# SensorTensao.net
KiCad netlist of a schematic drawn in EAGLE
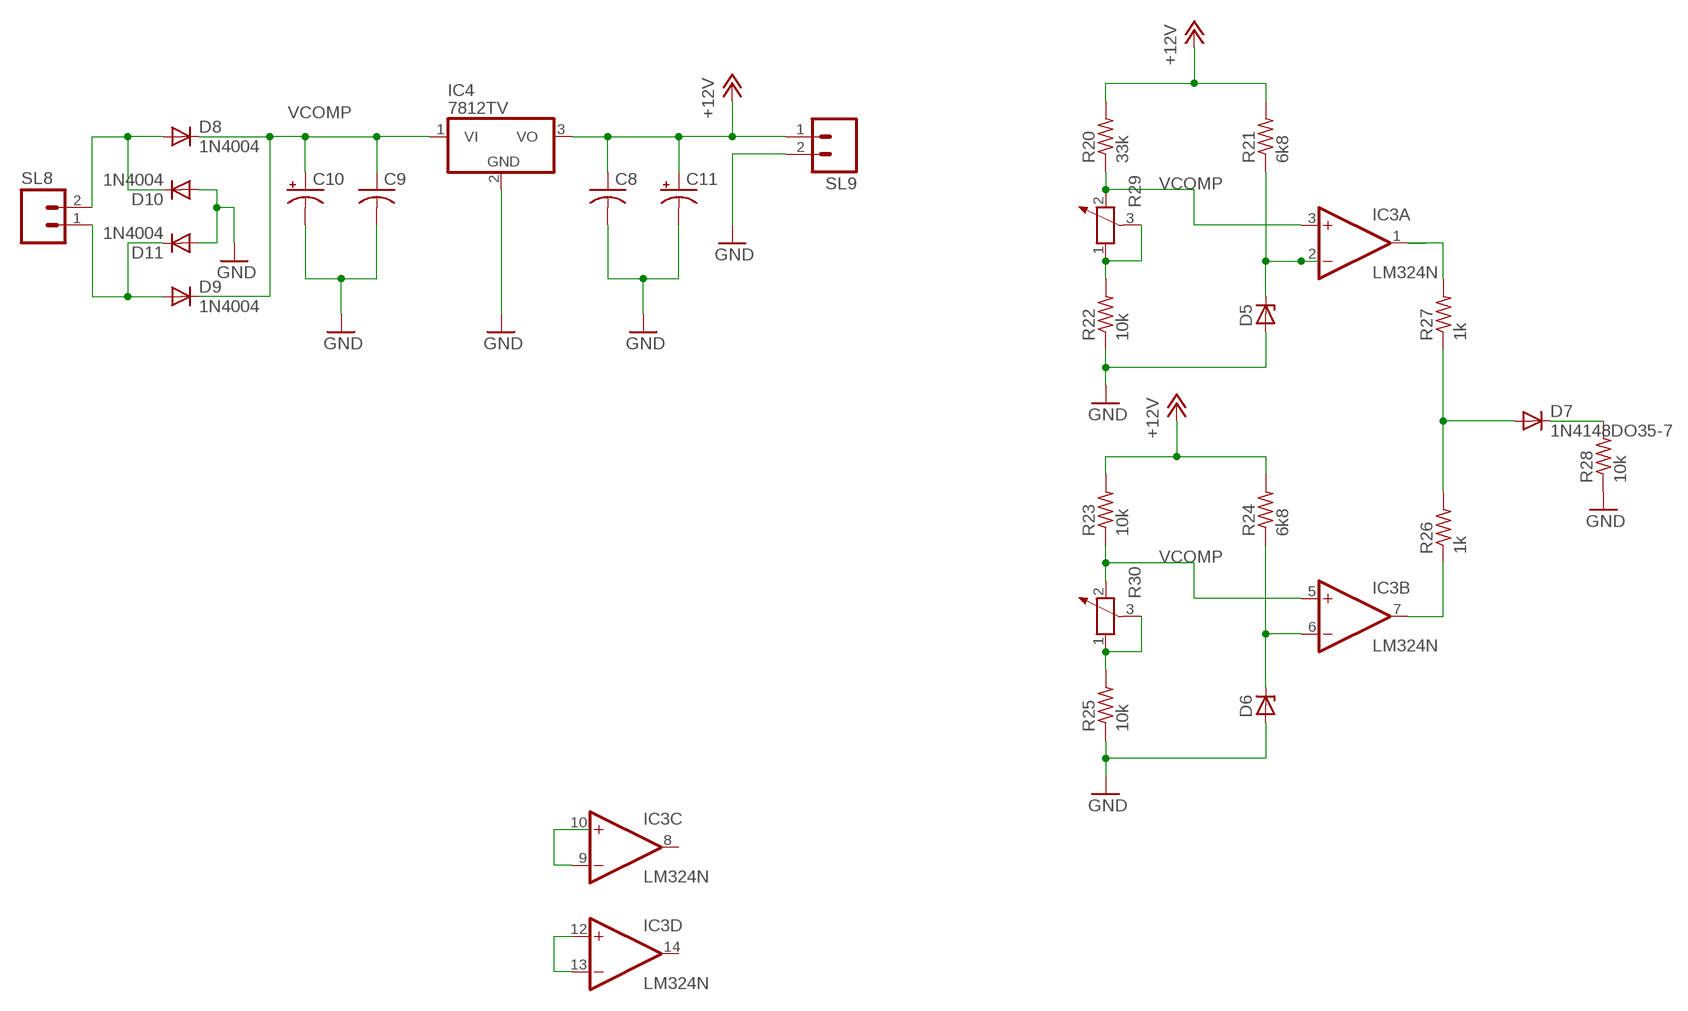
[diagram p0: schematic, sheet 1]

(export (version "E")
  (design (tool "Eeschema 10.0.6"))
  (components
    (comp (ref "C8")
      (value "C-US050-030X075")
      (footprint "eagle-import:C050-030X075")
      (libsource (lib "eagle-import") (part "C-US050-030X075"))
    )
    (comp (ref "C9")
      (value "C-US050-030X075")
      (footprint "eagle-import:C050-030X075")
      (libsource (lib "eagle-import") (part "C-US050-030X075"))
    )
    (comp (ref "C10")
      (value "CPOL-USE2.5-6")
      (footprint "eagle-import:E2,5-6")
      (libsource (lib "eagle-import") (part "CPOL-USE2.5-6"))
    )
    (comp (ref "C11")
      (value "CPOL-USE2.5-6")
      (footprint "eagle-import:E2,5-6")
      (libsource (lib "eagle-import") (part "CPOL-USE2.5-6"))
    )
    (comp (ref "D5")
      (value "ZENER-DIODEZD-7.5")
      (footprint "eagle-import:ZDIO-7.5")
      (libsource (lib "eagle-import") (part "ZENER-DIODEZD-7.5"))
    )
    (comp (ref "D6")
      (value "ZENER-DIODEZD-7.5")
      (footprint "eagle-import:ZDIO-7.5")
      (libsource (lib "eagle-import") (part "ZENER-DIODEZD-7.5"))
    )
    (comp (ref "D7")
      (value "1N4148DO35-7")
      (footprint "eagle-import:DO35-7")
      (libsource (lib "eagle-import") (part "1N4148DO35-7"))
    )
    (comp (ref "D8")
      (value "1N4004")
      (footprint "eagle-import:DO41-10")
      (libsource (lib "eagle-import") (part "1N4004"))
    )
    (comp (ref "D9")
      (value "1N4004")
      (footprint "eagle-import:DO41-10")
      (libsource (lib "eagle-import") (part "1N4004"))
    )
    (comp (ref "D10")
      (value "1N4004")
      (footprint "eagle-import:DO41-10")
      (libsource (lib "eagle-import") (part "1N4004"))
    )
    (comp (ref "D11")
      (value "1N4004")
      (footprint "eagle-import:DO41-10")
      (libsource (lib "eagle-import") (part "1N4004"))
    )
    (comp (ref "IC3")
      (value "LM324N")
      (footprint "eagle-import:DIL14")
      (libsource (lib "eagle-import") (part "LM324N"))
    )
    (comp (ref "IC4")
      (value "7812TV")
      (footprint "eagle-import:TO220V")
      (libsource (lib "eagle-import") (part "78TV12"))
    )
    (comp (ref "R20")
      (value "33k")
      (footprint "eagle-import:0204_7")
      (libsource (lib "eagle-import") (part "R-US_0204/7"))
    )
    (comp (ref "R21")
      (value "6k8")
      (footprint "eagle-import:0204_7")
      (libsource (lib "eagle-import") (part "R-US_0204/7"))
    )
    (comp (ref "R22")
      (value "10k")
      (footprint "eagle-import:0204_7")
      (libsource (lib "eagle-import") (part "R-US_0204/7"))
    )
    (comp (ref "R23")
      (value "10k")
      (footprint "eagle-import:0204_7")
      (libsource (lib "eagle-import") (part "R-US_0204/7"))
    )
    (comp (ref "R24")
      (value "6k8")
      (footprint "eagle-import:0204_7")
      (libsource (lib "eagle-import") (part "R-US_0204/7"))
    )
    (comp (ref "R25")
      (value "10k")
      (footprint "eagle-import:0204_7")
      (libsource (lib "eagle-import") (part "R-US_0204/7"))
    )
    (comp (ref "R26")
      (value "1k")
      (footprint "eagle-import:0204_7")
      (libsource (lib "eagle-import") (part "R-US_0204/7"))
    )
    (comp (ref "R27")
      (value "1k")
      (footprint "eagle-import:0204_7")
      (libsource (lib "eagle-import") (part "R-US_0204/7"))
    )
    (comp (ref "R28")
      (value "10k")
      (footprint "eagle-import:0204_7")
      (libsource (lib "eagle-import") (part "R-US_0204/7"))
    )
    (comp (ref "R29")
      (value "POTENTIOMETER_PT-10S")
      (footprint "eagle-import:PT-10S")
      (libsource (lib "eagle-import") (part "POTENTIOMETER_PT-10S"))
    )
    (comp (ref "R30")
      (value "POTENTIOMETER_PT-10S")
      (footprint "eagle-import:PT-10S")
      (libsource (lib "eagle-import") (part "POTENTIOMETER_PT-10S"))
    )
    (comp (ref "SL8")
      (value "M02")
      (footprint "eagle-import:02P")
      (libsource (lib "eagle-import") (part "M02"))
    )
    (comp (ref "SL9")
      (value "M02")
      (footprint "eagle-import:02P")
      (libsource (lib "eagle-import") (part "M02"))
    )
  )
  (nets
    (net (code "1") (name "+12V") (class "Default")
      (node (ref "C11") (pin "+") (pinfunction "+_+") (pintype "passive"))
      (node (ref "C8") (pin "1") (pinfunction "1_1") (pintype "passive"))
      (node (ref "IC4") (pin "3") (pinfunction "VO_3") (pintype "passive"))
      (node (ref "R20") (pin "2") (pinfunction "2_2") (pintype "passive"))
      (node (ref "R21") (pin "2") (pinfunction "2_2") (pintype "passive"))
      (node (ref "R23") (pin "2") (pinfunction "2_2") (pintype "passive"))
      (node (ref "R24") (pin "2") (pinfunction "2_2") (pintype "passive"))
      (node (ref "SL9") (pin "1") (pinfunction "1_1") (pintype "passive"))
    )
    (net (code "2") (name "/VCOMP") (class "Default")
      (node (ref "C10") (pin "+") (pinfunction "+_+") (pintype "passive"))
      (node (ref "C9") (pin "1") (pinfunction "1_1") (pintype "passive"))
      (node (ref "D8") (pin "C") (pinfunction "C_C") (pintype "passive"))
      (node (ref "D9") (pin "C") (pinfunction "C_C") (pintype "passive"))
      (node (ref "IC3") (pin "3") (pinfunction "+IN_3") (pintype "input"))
      (node (ref "IC3") (pin "5") (pinfunction "+IN_5") (pintype "input"))
      (node (ref "IC4") (pin "1") (pinfunction "VI_1") (pintype "input"))
      (node (ref "R20") (pin "1") (pinfunction "1_1") (pintype "passive"))
      (node (ref "R23") (pin "1") (pinfunction "1_1") (pintype "passive"))
      (node (ref "R29") (pin "2") (pinfunction "2_2") (pintype "passive"))
      (node (ref "R30") (pin "2") (pinfunction "2_2") (pintype "passive"))
    )
    (net (code "3") (name "GND") (class "Default")
      (node (ref "C10") (pin "-") (pinfunction "-_-") (pintype "passive"))
      (node (ref "C11") (pin "-") (pinfunction "-_-") (pintype "passive"))
      (node (ref "C8") (pin "2") (pinfunction "2_2") (pintype "passive"))
      (node (ref "C9") (pin "2") (pinfunction "2_2") (pintype "passive"))
      (node (ref "D10") (pin "A") (pinfunction "A_A") (pintype "passive"))
      (node (ref "D11") (pin "A") (pinfunction "A_A") (pintype "passive"))
      (node (ref "D5") (pin "A") (pinfunction "A_A") (pintype "passive"))
      (node (ref "D6") (pin "A") (pinfunction "A_A") (pintype "passive"))
      (node (ref "IC4") (pin "2") (pinfunction "GND_2") (pintype "passive"))
      (node (ref "R22") (pin "1") (pinfunction "1_1") (pintype "passive"))
      (node (ref "R25") (pin "1") (pinfunction "1_1") (pintype "passive"))
      (node (ref "R28") (pin "1") (pinfunction "1_1") (pintype "passive"))
      (node (ref "SL9") (pin "2") (pinfunction "2_2") (pintype "passive"))
    )
    (net (code "4") (name "Net-(D7-PadA)") (class "Default")
      (node (ref "D7") (pin "A") (pinfunction "A_A") (pintype "passive"))
      (node (ref "R26") (pin "2") (pinfunction "2_2") (pintype "passive"))
      (node (ref "R27") (pin "1") (pinfunction "1_1") (pintype "passive"))
    )
    (net (code "5") (name "Net-(D7-PadC)") (class "Default")
      (node (ref "D7") (pin "C") (pinfunction "C_C") (pintype "passive"))
      (node (ref "R28") (pin "2") (pinfunction "2_2") (pintype "passive"))
    )
    (net (code "6") (name "Net-(D10-PadC)") (class "Default")
      (node (ref "D10") (pin "C") (pinfunction "C_C") (pintype "passive"))
      (node (ref "D8") (pin "A") (pinfunction "A_A") (pintype "passive"))
      (node (ref "SL8") (pin "2") (pinfunction "2_2") (pintype "passive"))
    )
    (net (code "7") (name "Net-(D11-PadC)") (class "Default")
      (node (ref "D11") (pin "C") (pinfunction "C_C") (pintype "passive"))
      (node (ref "D9") (pin "A") (pinfunction "A_A") (pintype "passive"))
      (node (ref "SL8") (pin "1") (pinfunction "1_1") (pintype "passive"))
    )
    (net (code "8") (name "Net-(IC3A--IN)") (class "Default")
      (node (ref "D5") (pin "C") (pinfunction "C_C") (pintype "passive"))
      (node (ref "IC3") (pin "2") (pinfunction "-IN_2") (pintype "input"))
      (node (ref "R21") (pin "1") (pinfunction "1_1") (pintype "passive"))
    )
    (net (code "9") (name "Net-(IC3A-OUT)") (class "Default")
      (node (ref "IC3") (pin "1") (pinfunction "OUT_1") (pintype "output"))
      (node (ref "R27") (pin "2") (pinfunction "2_2") (pintype "passive"))
    )
    (net (code "10") (name "Net-(IC3B--IN)") (class "Default")
      (node (ref "D6") (pin "C") (pinfunction "C_C") (pintype "passive"))
      (node (ref "IC3") (pin "6") (pinfunction "-IN_6") (pintype "input"))
      (node (ref "R24") (pin "1") (pinfunction "1_1") (pintype "passive"))
    )
    (net (code "11") (name "Net-(IC3B-OUT)") (class "Default")
      (node (ref "IC3") (pin "7") (pinfunction "OUT_7") (pintype "output"))
      (node (ref "R26") (pin "1") (pinfunction "1_1") (pintype "passive"))
    )
    (net (code "12") (name "Net-(IC3D-+IN)") (class "Default")
      (node (ref "IC3") (pin "12") (pinfunction "+IN_12") (pintype "input"))
      (node (ref "IC3") (pin "13") (pinfunction "-IN_13") (pintype "input"))
    )
    (net (code "13") (name "Net-(R22-Pad2)") (class "Default")
      (node (ref "R22") (pin "2") (pinfunction "2_2") (pintype "passive"))
      (node (ref "R29") (pin "1") (pinfunction "1_1") (pintype "passive"))
      (node (ref "R29") (pin "3") (pinfunction "3_3") (pintype "passive"))
    )
    (net (code "14") (name "Net-(R25-Pad2)") (class "Default")
      (node (ref "R25") (pin "2") (pinfunction "2_2") (pintype "passive"))
      (node (ref "R30") (pin "1") (pinfunction "1_1") (pintype "passive"))
      (node (ref "R30") (pin "3") (pinfunction "3_3") (pintype "passive"))
    )
    (net (code "15") (name "unconnected-(IC3C-+IN-Pad10)") (class "Default")
      (node (ref "IC3") (pin "10") (pinfunction "+IN_10") (pintype "input"))
    )
    (net (code "16") (name "unconnected-(IC3C--IN-Pad9)") (class "Default")
      (node (ref "IC3") (pin "9") (pinfunction "-IN_9") (pintype "input"))
    )
    (net (code "17") (name "unconnected-(IC3C-OUT-Pad8)") (class "Default")
      (node (ref "IC3") (pin "8") (pinfunction "OUT_8") (pintype "output"))
    )
    (net (code "18") (name "unconnected-(IC3D-OUT-Pad14)") (class "Default")
      (node (ref "IC3") (pin "14") (pinfunction "OUT_14") (pintype "output"))
    )
  )
)
